# matchbox_bob_v10.net
KiCad netlist of a schematic drawn in EAGLE
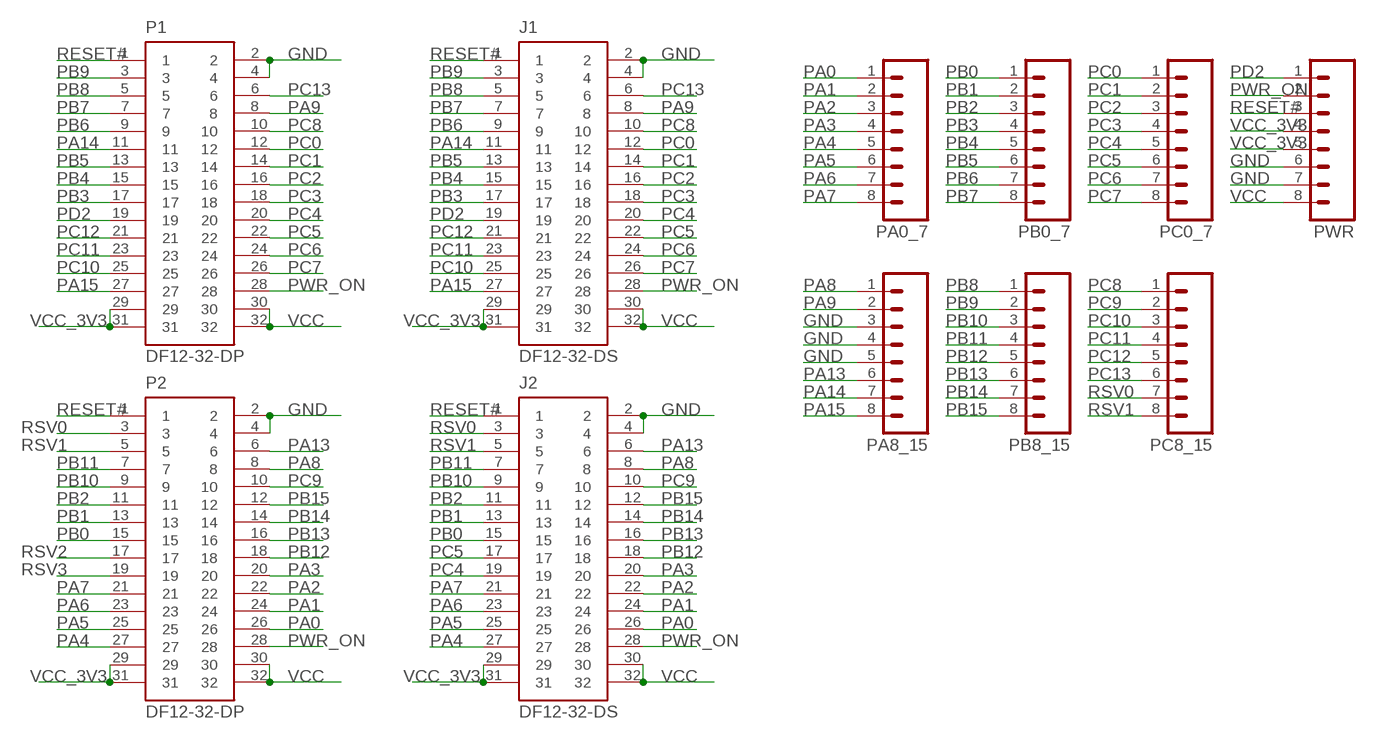
[diagram p0: schematic, sheet 1]

(export (version "E")
  (design (tool "Eeschema 10.0.6"))
  (components
    (comp (ref "J1")
      (value "DF12-32-DS")
      (footprint "eagle-import:DF12-32-DS")
      (fields (field (name "PARTNO") "AS-ITM-00012"))
      (libsource (lib "eagle-import") (part "AS-ITM-00012"))
    )
    (comp (ref "J2")
      (value "DF12-32-DS")
      (footprint "eagle-import:DF12-32-DS")
      (fields (field (name "PARTNO") "AS-ITM-00012"))
      (libsource (lib "eagle-import") (part "AS-ITM-00012"))
    )
    (comp (ref "P1")
      (value "DF12-32-DP")
      (footprint "eagle-import:DF12-32-DP")
      (fields (field (name "PARTNO") "AS-ITM-00015"))
      (libsource (lib "eagle-import") (part "AS-ITM-00015"))
    )
    (comp (ref "P2")
      (value "DF12-32-DP")
      (footprint "eagle-import:DF12-32-DP")
      (fields (field (name "PARTNO") "AS-ITM-00015"))
      (libsource (lib "eagle-import") (part "AS-ITM-00015"))
    )
    (comp (ref "PA0_7")
      (value "M08FEMALE_LOCK")
      (footprint "eagle-import:1X08_FEMALE_LOCK")
      (libsource (lib "eagle-import") (part "M08FEMALE_LOCK"))
    )
    (comp (ref "PA8_15")
      (value "M08FEMALE_LOCK")
      (footprint "eagle-import:1X08_FEMALE_LOCK")
      (libsource (lib "eagle-import") (part "M08FEMALE_LOCK"))
    )
    (comp (ref "PB0_7")
      (value "M08FEMALE_LOCK")
      (footprint "eagle-import:1X08_FEMALE_LOCK")
      (libsource (lib "eagle-import") (part "M08FEMALE_LOCK"))
    )
    (comp (ref "PB8_15")
      (value "M08FEMALE_LOCK")
      (footprint "eagle-import:1X08_FEMALE_LOCK")
      (libsource (lib "eagle-import") (part "M08FEMALE_LOCK"))
    )
    (comp (ref "PC0_7")
      (value "M08FEMALE_LOCK")
      (footprint "eagle-import:1X08_FEMALE_LOCK")
      (libsource (lib "eagle-import") (part "M08FEMALE_LOCK"))
    )
    (comp (ref "PC8_15")
      (value "M08FEMALE_LOCK")
      (footprint "eagle-import:1X08_FEMALE_LOCK")
      (libsource (lib "eagle-import") (part "M08FEMALE_LOCK"))
    )
    (comp (ref "PWR")
      (value "M08FEMALE_LOCK")
      (footprint "eagle-import:1X08_FEMALE_LOCK")
      (libsource (lib "eagle-import") (part "M08FEMALE_LOCK"))
    )
  )
  (nets
    (net (code "1") (name "/GND") (class "Default")
      (node (ref "J1") (pin "2") (pinfunction "2_2") (pintype "bidirectional"))
      (node (ref "J1") (pin "4") (pinfunction "4_4") (pintype "bidirectional"))
      (node (ref "J2") (pin "2") (pinfunction "2_2") (pintype "bidirectional"))
      (node (ref "J2") (pin "4") (pinfunction "4_4") (pintype "bidirectional"))
      (node (ref "P1") (pin "2") (pinfunction "2_2") (pintype "bidirectional"))
      (node (ref "P1") (pin "4") (pinfunction "4_4") (pintype "bidirectional"))
      (node (ref "P2") (pin "2") (pinfunction "2_2") (pintype "bidirectional"))
      (node (ref "P2") (pin "4") (pinfunction "4_4") (pintype "bidirectional"))
      (node (ref "PA8_15") (pin "3") (pinfunction "3_3") (pintype "passive"))
      (node (ref "PA8_15") (pin "4") (pinfunction "4_4") (pintype "passive"))
      (node (ref "PA8_15") (pin "5") (pinfunction "5_5") (pintype "passive"))
      (node (ref "PWR") (pin "6") (pinfunction "6_6") (pintype "passive"))
      (node (ref "PWR") (pin "7") (pinfunction "7_7") (pintype "passive"))
    )
    (net (code "2") (name "/PA0") (class "Default")
      (node (ref "J2") (pin "26") (pinfunction "26_26") (pintype "bidirectional"))
      (node (ref "P2") (pin "26") (pinfunction "26_26") (pintype "bidirectional"))
      (node (ref "PA0_7") (pin "1") (pinfunction "1_1") (pintype "passive"))
    )
    (net (code "3") (name "/PA1") (class "Default")
      (node (ref "J2") (pin "24") (pinfunction "24_24") (pintype "bidirectional"))
      (node (ref "P2") (pin "24") (pinfunction "24_24") (pintype "bidirectional"))
      (node (ref "PA0_7") (pin "2") (pinfunction "2_2") (pintype "passive"))
    )
    (net (code "4") (name "/PA2") (class "Default")
      (node (ref "J2") (pin "22") (pinfunction "22_22") (pintype "bidirectional"))
      (node (ref "P2") (pin "22") (pinfunction "22_22") (pintype "bidirectional"))
      (node (ref "PA0_7") (pin "3") (pinfunction "3_3") (pintype "passive"))
    )
    (net (code "5") (name "/PA3") (class "Default")
      (node (ref "J2") (pin "20") (pinfunction "20_20") (pintype "bidirectional"))
      (node (ref "P2") (pin "20") (pinfunction "20_20") (pintype "bidirectional"))
      (node (ref "PA0_7") (pin "4") (pinfunction "4_4") (pintype "passive"))
    )
    (net (code "6") (name "/PA4") (class "Default")
      (node (ref "J2") (pin "27") (pinfunction "27_27") (pintype "bidirectional"))
      (node (ref "P2") (pin "27") (pinfunction "27_27") (pintype "bidirectional"))
      (node (ref "PA0_7") (pin "5") (pinfunction "5_5") (pintype "passive"))
    )
    (net (code "7") (name "/PA5") (class "Default")
      (node (ref "J2") (pin "25") (pinfunction "25_25") (pintype "bidirectional"))
      (node (ref "P2") (pin "25") (pinfunction "25_25") (pintype "bidirectional"))
      (node (ref "PA0_7") (pin "6") (pinfunction "6_6") (pintype "passive"))
    )
    (net (code "8") (name "/PA6") (class "Default")
      (node (ref "J2") (pin "23") (pinfunction "23_23") (pintype "bidirectional"))
      (node (ref "P2") (pin "23") (pinfunction "23_23") (pintype "bidirectional"))
      (node (ref "PA0_7") (pin "7") (pinfunction "7_7") (pintype "passive"))
    )
    (net (code "9") (name "/PA7") (class "Default")
      (node (ref "J2") (pin "21") (pinfunction "21_21") (pintype "bidirectional"))
      (node (ref "P2") (pin "21") (pinfunction "21_21") (pintype "bidirectional"))
      (node (ref "PA0_7") (pin "8") (pinfunction "8_8") (pintype "passive"))
    )
    (net (code "10") (name "/PA8") (class "Default")
      (node (ref "J2") (pin "8") (pinfunction "8_8") (pintype "bidirectional"))
      (node (ref "P2") (pin "8") (pinfunction "8_8") (pintype "bidirectional"))
      (node (ref "PA8_15") (pin "1") (pinfunction "1_1") (pintype "passive"))
    )
    (net (code "11") (name "/PA9") (class "Default")
      (node (ref "J1") (pin "8") (pinfunction "8_8") (pintype "bidirectional"))
      (node (ref "P1") (pin "8") (pinfunction "8_8") (pintype "bidirectional"))
      (node (ref "PA8_15") (pin "2") (pinfunction "2_2") (pintype "passive"))
    )
    (net (code "12") (name "/PA13") (class "Default")
      (node (ref "J2") (pin "6") (pinfunction "6_6") (pintype "bidirectional"))
      (node (ref "P2") (pin "6") (pinfunction "6_6") (pintype "bidirectional"))
      (node (ref "PA8_15") (pin "6") (pinfunction "6_6") (pintype "passive"))
    )
    (net (code "13") (name "/PA14") (class "Default")
      (node (ref "J1") (pin "11") (pinfunction "11_11") (pintype "bidirectional"))
      (node (ref "P1") (pin "11") (pinfunction "11_11") (pintype "bidirectional"))
      (node (ref "PA8_15") (pin "7") (pinfunction "7_7") (pintype "passive"))
    )
    (net (code "14") (name "/PA15") (class "Default")
      (node (ref "J1") (pin "27") (pinfunction "27_27") (pintype "bidirectional"))
      (node (ref "P1") (pin "27") (pinfunction "27_27") (pintype "bidirectional"))
      (node (ref "PA8_15") (pin "8") (pinfunction "8_8") (pintype "passive"))
    )
    (net (code "15") (name "/PB0") (class "Default")
      (node (ref "J2") (pin "15") (pinfunction "15_15") (pintype "bidirectional"))
      (node (ref "P2") (pin "15") (pinfunction "15_15") (pintype "bidirectional"))
      (node (ref "PB0_7") (pin "1") (pinfunction "1_1") (pintype "passive"))
    )
    (net (code "16") (name "/PB1") (class "Default")
      (node (ref "J2") (pin "13") (pinfunction "13_13") (pintype "bidirectional"))
      (node (ref "P2") (pin "13") (pinfunction "13_13") (pintype "bidirectional"))
      (node (ref "PB0_7") (pin "2") (pinfunction "2_2") (pintype "passive"))
    )
    (net (code "17") (name "/PB2") (class "Default")
      (node (ref "J2") (pin "11") (pinfunction "11_11") (pintype "bidirectional"))
      (node (ref "P2") (pin "11") (pinfunction "11_11") (pintype "bidirectional"))
      (node (ref "PB0_7") (pin "3") (pinfunction "3_3") (pintype "passive"))
    )
    (net (code "18") (name "/PB3") (class "Default")
      (node (ref "J1") (pin "17") (pinfunction "17_17") (pintype "bidirectional"))
      (node (ref "P1") (pin "17") (pinfunction "17_17") (pintype "bidirectional"))
      (node (ref "PB0_7") (pin "4") (pinfunction "4_4") (pintype "passive"))
    )
    (net (code "19") (name "/PB4") (class "Default")
      (node (ref "J1") (pin "15") (pinfunction "15_15") (pintype "bidirectional"))
      (node (ref "P1") (pin "15") (pinfunction "15_15") (pintype "bidirectional"))
      (node (ref "PB0_7") (pin "5") (pinfunction "5_5") (pintype "passive"))
    )
    (net (code "20") (name "/PB5") (class "Default")
      (node (ref "J1") (pin "13") (pinfunction "13_13") (pintype "bidirectional"))
      (node (ref "P1") (pin "13") (pinfunction "13_13") (pintype "bidirectional"))
      (node (ref "PB0_7") (pin "6") (pinfunction "6_6") (pintype "passive"))
    )
    (net (code "21") (name "/PB6") (class "Default")
      (node (ref "J1") (pin "9") (pinfunction "9_9") (pintype "bidirectional"))
      (node (ref "P1") (pin "9") (pinfunction "9_9") (pintype "bidirectional"))
      (node (ref "PB0_7") (pin "7") (pinfunction "7_7") (pintype "passive"))
    )
    (net (code "22") (name "/PB7") (class "Default")
      (node (ref "J1") (pin "7") (pinfunction "7_7") (pintype "bidirectional"))
      (node (ref "P1") (pin "7") (pinfunction "7_7") (pintype "bidirectional"))
      (node (ref "PB0_7") (pin "8") (pinfunction "8_8") (pintype "passive"))
    )
    (net (code "23") (name "/PB8") (class "Default")
      (node (ref "J1") (pin "5") (pinfunction "5_5") (pintype "bidirectional"))
      (node (ref "P1") (pin "5") (pinfunction "5_5") (pintype "bidirectional"))
      (node (ref "PB8_15") (pin "1") (pinfunction "1_1") (pintype "passive"))
    )
    (net (code "24") (name "/PB9") (class "Default")
      (node (ref "J1") (pin "3") (pinfunction "3_3") (pintype "bidirectional"))
      (node (ref "P1") (pin "3") (pinfunction "3_3") (pintype "bidirectional"))
      (node (ref "PB8_15") (pin "2") (pinfunction "2_2") (pintype "passive"))
    )
    (net (code "25") (name "/PB10") (class "Default")
      (node (ref "J2") (pin "9") (pinfunction "9_9") (pintype "bidirectional"))
      (node (ref "P2") (pin "9") (pinfunction "9_9") (pintype "bidirectional"))
      (node (ref "PB8_15") (pin "3") (pinfunction "3_3") (pintype "passive"))
    )
    (net (code "26") (name "/PB11") (class "Default")
      (node (ref "J2") (pin "7") (pinfunction "7_7") (pintype "bidirectional"))
      (node (ref "P2") (pin "7") (pinfunction "7_7") (pintype "bidirectional"))
      (node (ref "PB8_15") (pin "4") (pinfunction "4_4") (pintype "passive"))
    )
    (net (code "27") (name "/PB12") (class "Default")
      (node (ref "J2") (pin "18") (pinfunction "18_18") (pintype "bidirectional"))
      (node (ref "P2") (pin "18") (pinfunction "18_18") (pintype "bidirectional"))
      (node (ref "PB8_15") (pin "5") (pinfunction "5_5") (pintype "passive"))
    )
    (net (code "28") (name "/PB13") (class "Default")
      (node (ref "J2") (pin "16") (pinfunction "16_16") (pintype "bidirectional"))
      (node (ref "P2") (pin "16") (pinfunction "16_16") (pintype "bidirectional"))
      (node (ref "PB8_15") (pin "6") (pinfunction "6_6") (pintype "passive"))
    )
    (net (code "29") (name "/PB14") (class "Default")
      (node (ref "J2") (pin "14") (pinfunction "14_14") (pintype "bidirectional"))
      (node (ref "P2") (pin "14") (pinfunction "14_14") (pintype "bidirectional"))
      (node (ref "PB8_15") (pin "7") (pinfunction "7_7") (pintype "passive"))
    )
    (net (code "30") (name "/PB15") (class "Default")
      (node (ref "J2") (pin "12") (pinfunction "12_12") (pintype "bidirectional"))
      (node (ref "P2") (pin "12") (pinfunction "12_12") (pintype "bidirectional"))
      (node (ref "PB8_15") (pin "8") (pinfunction "8_8") (pintype "passive"))
    )
    (net (code "31") (name "/PC0") (class "Default")
      (node (ref "J1") (pin "12") (pinfunction "12_12") (pintype "bidirectional"))
      (node (ref "P1") (pin "12") (pinfunction "12_12") (pintype "bidirectional"))
      (node (ref "PC0_7") (pin "1") (pinfunction "1_1") (pintype "passive"))
    )
    (net (code "32") (name "/PC1") (class "Default")
      (node (ref "J1") (pin "14") (pinfunction "14_14") (pintype "bidirectional"))
      (node (ref "P1") (pin "14") (pinfunction "14_14") (pintype "bidirectional"))
      (node (ref "PC0_7") (pin "2") (pinfunction "2_2") (pintype "passive"))
    )
    (net (code "33") (name "/PC2") (class "Default")
      (node (ref "J1") (pin "16") (pinfunction "16_16") (pintype "bidirectional"))
      (node (ref "P1") (pin "16") (pinfunction "16_16") (pintype "bidirectional"))
      (node (ref "PC0_7") (pin "3") (pinfunction "3_3") (pintype "passive"))
    )
    (net (code "34") (name "/PC3") (class "Default")
      (node (ref "J1") (pin "18") (pinfunction "18_18") (pintype "bidirectional"))
      (node (ref "P1") (pin "18") (pinfunction "18_18") (pintype "bidirectional"))
      (node (ref "PC0_7") (pin "4") (pinfunction "4_4") (pintype "passive"))
    )
    (net (code "35") (name "/PC4") (class "Default")
      (node (ref "J1") (pin "20") (pinfunction "20_20") (pintype "bidirectional"))
      (node (ref "J2") (pin "19") (pinfunction "19_19") (pintype "bidirectional"))
      (node (ref "P1") (pin "20") (pinfunction "20_20") (pintype "bidirectional"))
      (node (ref "PC0_7") (pin "5") (pinfunction "5_5") (pintype "passive"))
    )
    (net (code "36") (name "/PC5") (class "Default")
      (node (ref "J1") (pin "22") (pinfunction "22_22") (pintype "bidirectional"))
      (node (ref "J2") (pin "17") (pinfunction "17_17") (pintype "bidirectional"))
      (node (ref "P1") (pin "22") (pinfunction "22_22") (pintype "bidirectional"))
      (node (ref "PC0_7") (pin "6") (pinfunction "6_6") (pintype "passive"))
    )
    (net (code "37") (name "/PC6") (class "Default")
      (node (ref "J1") (pin "24") (pinfunction "24_24") (pintype "bidirectional"))
      (node (ref "P1") (pin "24") (pinfunction "24_24") (pintype "bidirectional"))
      (node (ref "PC0_7") (pin "7") (pinfunction "7_7") (pintype "passive"))
    )
    (net (code "38") (name "/PC7") (class "Default")
      (node (ref "J1") (pin "26") (pinfunction "26_26") (pintype "bidirectional"))
      (node (ref "P1") (pin "26") (pinfunction "26_26") (pintype "bidirectional"))
      (node (ref "PC0_7") (pin "8") (pinfunction "8_8") (pintype "passive"))
    )
    (net (code "39") (name "/PC8") (class "Default")
      (node (ref "J1") (pin "10") (pinfunction "10_10") (pintype "bidirectional"))
      (node (ref "P1") (pin "10") (pinfunction "10_10") (pintype "bidirectional"))
      (node (ref "PC8_15") (pin "1") (pinfunction "1_1") (pintype "passive"))
    )
    (net (code "40") (name "/PC9") (class "Default")
      (node (ref "J2") (pin "10") (pinfunction "10_10") (pintype "bidirectional"))
      (node (ref "P2") (pin "10") (pinfunction "10_10") (pintype "bidirectional"))
      (node (ref "PC8_15") (pin "2") (pinfunction "2_2") (pintype "passive"))
    )
    (net (code "41") (name "/PC10") (class "Default")
      (node (ref "J1") (pin "25") (pinfunction "25_25") (pintype "bidirectional"))
      (node (ref "P1") (pin "25") (pinfunction "25_25") (pintype "bidirectional"))
      (node (ref "PC8_15") (pin "3") (pinfunction "3_3") (pintype "passive"))
    )
    (net (code "42") (name "/PC11") (class "Default")
      (node (ref "J1") (pin "23") (pinfunction "23_23") (pintype "bidirectional"))
      (node (ref "P1") (pin "23") (pinfunction "23_23") (pintype "bidirectional"))
      (node (ref "PC8_15") (pin "4") (pinfunction "4_4") (pintype "passive"))
    )
    (net (code "43") (name "/PC12") (class "Default")
      (node (ref "J1") (pin "21") (pinfunction "21_21") (pintype "bidirectional"))
      (node (ref "P1") (pin "21") (pinfunction "21_21") (pintype "bidirectional"))
      (node (ref "PC8_15") (pin "5") (pinfunction "5_5") (pintype "passive"))
    )
    (net (code "44") (name "/PC13") (class "Default")
      (node (ref "J1") (pin "6") (pinfunction "6_6") (pintype "bidirectional"))
      (node (ref "P1") (pin "6") (pinfunction "6_6") (pintype "bidirectional"))
      (node (ref "PC8_15") (pin "6") (pinfunction "6_6") (pintype "passive"))
    )
    (net (code "45") (name "/PD2") (class "Default")
      (node (ref "J1") (pin "19") (pinfunction "19_19") (pintype "bidirectional"))
      (node (ref "P1") (pin "19") (pinfunction "19_19") (pintype "bidirectional"))
      (node (ref "PWR") (pin "1") (pinfunction "1_1") (pintype "passive"))
    )
    (net (code "46") (name "/PWR_ON") (class "Default")
      (node (ref "J1") (pin "28") (pinfunction "28_28") (pintype "bidirectional"))
      (node (ref "J2") (pin "28") (pinfunction "28_28") (pintype "bidirectional"))
      (node (ref "P1") (pin "28") (pinfunction "28_28") (pintype "bidirectional"))
      (node (ref "P2") (pin "28") (pinfunction "28_28") (pintype "bidirectional"))
      (node (ref "PWR") (pin "2") (pinfunction "2_2") (pintype "passive"))
    )
    (net (code "47") (name "/RESET#") (class "Default")
      (node (ref "J1") (pin "1") (pinfunction "1_1") (pintype "bidirectional"))
      (node (ref "J2") (pin "1") (pinfunction "1_1") (pintype "bidirectional"))
      (node (ref "P1") (pin "1") (pinfunction "1_1") (pintype "bidirectional"))
      (node (ref "P2") (pin "1") (pinfunction "1_1") (pintype "bidirectional"))
      (node (ref "PWR") (pin "3") (pinfunction "3_3") (pintype "passive"))
    )
    (net (code "48") (name "/RSV0") (class "Default")
      (node (ref "J2") (pin "3") (pinfunction "3_3") (pintype "bidirectional"))
      (node (ref "P2") (pin "3") (pinfunction "3_3") (pintype "bidirectional"))
      (node (ref "PC8_15") (pin "7") (pinfunction "7_7") (pintype "passive"))
    )
    (net (code "49") (name "/RSV1") (class "Default")
      (node (ref "J2") (pin "5") (pinfunction "5_5") (pintype "bidirectional"))
      (node (ref "P2") (pin "5") (pinfunction "5_5") (pintype "bidirectional"))
      (node (ref "PC8_15") (pin "8") (pinfunction "8_8") (pintype "passive"))
    )
    (net (code "50") (name "/RSV2") (class "Default")
      (node (ref "P2") (pin "17") (pinfunction "17_17") (pintype "bidirectional"))
    )
    (net (code "51") (name "/RSV3") (class "Default")
      (node (ref "P2") (pin "19") (pinfunction "19_19") (pintype "bidirectional"))
    )
    (net (code "52") (name "/VCC") (class "Default")
      (node (ref "J1") (pin "30") (pinfunction "30_30") (pintype "bidirectional"))
      (node (ref "J1") (pin "32") (pinfunction "32_32") (pintype "bidirectional"))
      (node (ref "J2") (pin "30") (pinfunction "30_30") (pintype "bidirectional"))
      (node (ref "J2") (pin "32") (pinfunction "32_32") (pintype "bidirectional"))
      (node (ref "P1") (pin "30") (pinfunction "30_30") (pintype "bidirectional"))
      (node (ref "P1") (pin "32") (pinfunction "32_32") (pintype "bidirectional"))
      (node (ref "P2") (pin "30") (pinfunction "30_30") (pintype "bidirectional"))
      (node (ref "P2") (pin "32") (pinfunction "32_32") (pintype "bidirectional"))
      (node (ref "PWR") (pin "8") (pinfunction "8_8") (pintype "passive"))
    )
    (net (code "53") (name "/VCC_3V3") (class "Default")
      (node (ref "J1") (pin "29") (pinfunction "29_29") (pintype "bidirectional"))
      (node (ref "J1") (pin "31") (pinfunction "31_31") (pintype "bidirectional"))
      (node (ref "J2") (pin "29") (pinfunction "29_29") (pintype "bidirectional"))
      (node (ref "J2") (pin "31") (pinfunction "31_31") (pintype "bidirectional"))
      (node (ref "P1") (pin "29") (pinfunction "29_29") (pintype "bidirectional"))
      (node (ref "P1") (pin "31") (pinfunction "31_31") (pintype "bidirectional"))
      (node (ref "P2") (pin "29") (pinfunction "29_29") (pintype "bidirectional"))
      (node (ref "P2") (pin "31") (pinfunction "31_31") (pintype "bidirectional"))
      (node (ref "PWR") (pin "4") (pinfunction "4_4") (pintype "passive"))
      (node (ref "PWR") (pin "5") (pinfunction "5_5") (pintype "passive"))
    )
  )
)
